# Main.net
KiCad netlist of a schematic drawn in Altium Designer
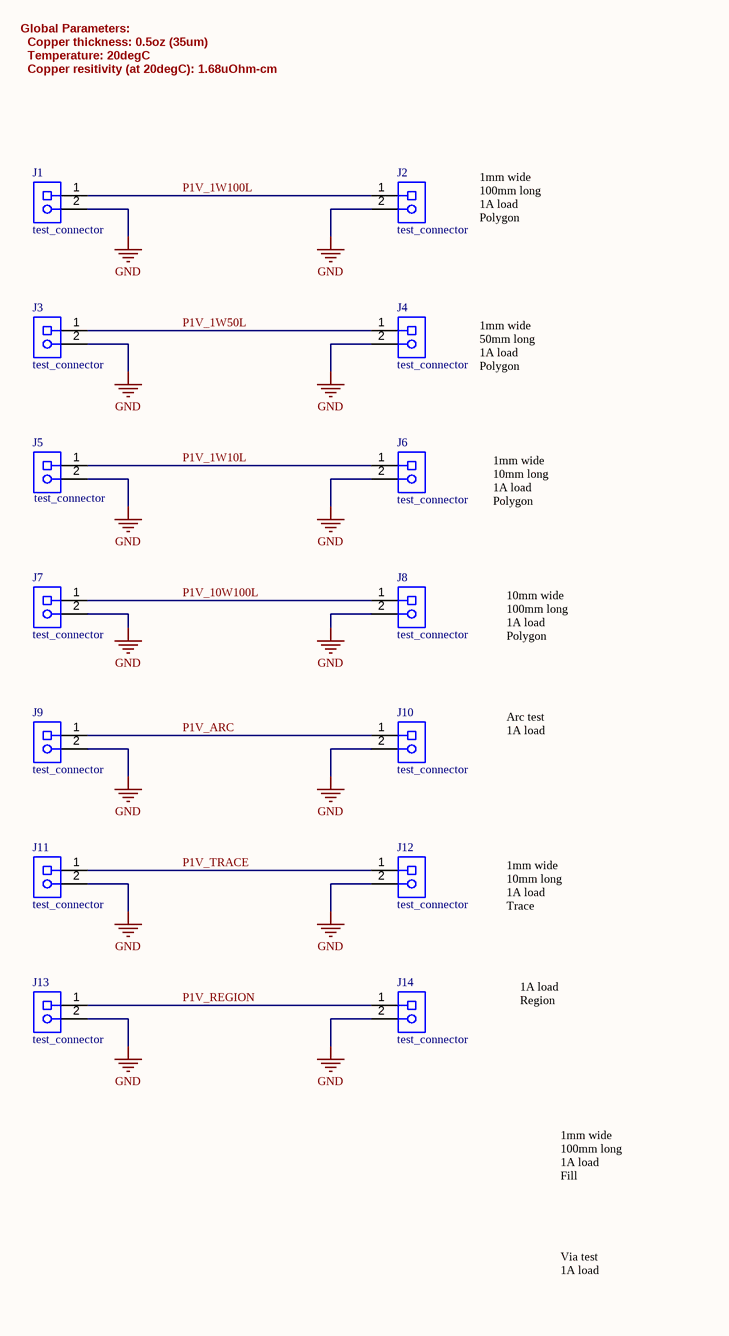
[diagram p0: Main.SchDoc]

(export (version "E")
  (design (tool "Eeschema 10.0.6"))
  (components
    (comp (ref "J1")
      (value "test_connector")
      (footprint "test_connector_footprint")
      (description "for playing around with")
      (fields
        (field (name "MANUFACTURER") "Phoenix Contact")
        (field (name "MANUFACTURER PART NUMBER") "1729128")
      )
      (libsource (lib "Sandbox") (part "test_conn"))
    )
    (comp (ref "J2")
      (value "test_connector")
      (footprint "test_connector_footprint")
      (description "for playing around with")
      (fields
        (field (name "MANUFACTURER") "Phoenix Contact")
        (field (name "MANUFACTURER PART NUMBER") "1729128")
      )
      (libsource (lib "") (part "test_conn_1"))
    )
    (comp (ref "J3")
      (value "test_connector")
      (footprint "test_connector_footprint")
      (description "for playing around with")
      (fields
        (field (name "MANUFACTURER") "Phoenix Contact")
        (field (name "MANUFACTURER PART NUMBER") "1729128")
      )
      (libsource (lib "Sandbox") (part "test_conn"))
    )
    (comp (ref "J4")
      (value "test_connector")
      (footprint "test_connector_footprint")
      (description "for playing around with")
      (fields
        (field (name "MANUFACTURER") "Phoenix Contact")
        (field (name "MANUFACTURER PART NUMBER") "1729128")
      )
      (libsource (lib "") (part "test_conn_1"))
    )
    (comp (ref "J5")
      (value "test_connector")
      (footprint "test_connector_footprint")
      (description "for playing around with")
      (fields
        (field (name "MANUFACTURER") "Phoenix Contact")
        (field (name "MANUFACTURER PART NUMBER") "1729128")
      )
      (libsource (lib "Sandbox") (part "test_conn"))
    )
    (comp (ref "J6")
      (value "test_connector")
      (footprint "test_connector_footprint")
      (description "for playing around with")
      (fields
        (field (name "MANUFACTURER") "Phoenix Contact")
        (field (name "MANUFACTURER PART NUMBER") "1729128")
      )
      (libsource (lib "") (part "test_conn_1"))
    )
    (comp (ref "J7")
      (value "test_connector")
      (footprint "test_connector_footprint")
      (description "for playing around with")
      (fields
        (field (name "MANUFACTURER") "Phoenix Contact")
        (field (name "MANUFACTURER PART NUMBER") "1729128")
      )
      (libsource (lib "Sandbox") (part "test_conn"))
    )
    (comp (ref "J8")
      (value "test_connector")
      (footprint "test_connector_footprint")
      (description "for playing around with")
      (fields
        (field (name "MANUFACTURER") "Phoenix Contact")
        (field (name "MANUFACTURER PART NUMBER") "1729128")
      )
      (libsource (lib "") (part "test_conn_1"))
    )
    (comp (ref "J9")
      (value "test_connector")
      (footprint "test_connector_footprint")
      (description "for playing around with")
      (fields
        (field (name "MANUFACTURER") "Phoenix Contact")
        (field (name "MANUFACTURER PART NUMBER") "1729128")
      )
      (libsource (lib "Sandbox") (part "test_conn"))
    )
    (comp (ref "J10")
      (value "test_connector")
      (footprint "test_connector_footprint")
      (description "for playing around with")
      (fields
        (field (name "MANUFACTURER") "Phoenix Contact")
        (field (name "MANUFACTURER PART NUMBER") "1729128")
      )
      (libsource (lib "") (part "test_conn_1"))
    )
    (comp (ref "J11")
      (value "test_connector")
      (footprint "test_connector_footprint")
      (description "for playing around with")
      (fields
        (field (name "MANUFACTURER") "Phoenix Contact")
        (field (name "MANUFACTURER PART NUMBER") "1729128")
      )
      (libsource (lib "Sandbox") (part "test_conn"))
    )
    (comp (ref "J12")
      (value "test_connector")
      (footprint "test_connector_footprint")
      (description "for playing around with")
      (fields
        (field (name "MANUFACTURER") "Phoenix Contact")
        (field (name "MANUFACTURER PART NUMBER") "1729128")
      )
      (libsource (lib "") (part "test_conn_1"))
    )
    (comp (ref "J13")
      (value "test_connector")
      (footprint "test_connector_footprint")
      (description "for playing around with")
      (fields
        (field (name "MANUFACTURER") "Phoenix Contact")
        (field (name "MANUFACTURER PART NUMBER") "1729128")
      )
      (libsource (lib "Sandbox") (part "test_conn"))
    )
    (comp (ref "J14")
      (value "test_connector")
      (footprint "test_connector_footprint")
      (description "for playing around with")
      (fields
        (field (name "MANUFACTURER") "Phoenix Contact")
        (field (name "MANUFACTURER PART NUMBER") "1729128")
      )
      (libsource (lib "") (part "test_conn_1"))
    )
  )
  (nets
    (net (code "1") (name "/P1V_1W10L") (class "Default")
      (node (ref "J5") (pin "1") (pinfunction "1_1") (pintype "passive"))
      (node (ref "J6") (pin "1") (pinfunction "1_1") (pintype "passive"))
    )
    (net (code "2") (name "/P1V_1W50L") (class "Default")
      (node (ref "J3") (pin "1") (pinfunction "1_1") (pintype "passive"))
      (node (ref "J4") (pin "1") (pinfunction "1_1") (pintype "passive"))
    )
    (net (code "3") (name "/P1V_1W100L") (class "Default")
      (node (ref "J1") (pin "1") (pinfunction "1_1") (pintype "passive"))
      (node (ref "J2") (pin "1") (pinfunction "1_1") (pintype "passive"))
    )
    (net (code "4") (name "/P1V_10W100L") (class "Default")
      (node (ref "J7") (pin "1") (pinfunction "1_1") (pintype "passive"))
      (node (ref "J8") (pin "1") (pinfunction "1_1") (pintype "passive"))
    )
    (net (code "5") (name "/P1V_ARC") (class "Default")
      (node (ref "J10") (pin "1") (pinfunction "1_1") (pintype "passive"))
      (node (ref "J9") (pin "1") (pinfunction "1_1") (pintype "passive"))
    )
    (net (code "6") (name "/P1V_REGION") (class "Default")
      (node (ref "J13") (pin "1") (pinfunction "1_1") (pintype "passive"))
      (node (ref "J14") (pin "1") (pinfunction "1_1") (pintype "passive"))
    )
    (net (code "7") (name "/P1V_TRACE") (class "Default")
      (node (ref "J11") (pin "1") (pinfunction "1_1") (pintype "passive"))
      (node (ref "J12") (pin "1") (pinfunction "1_1") (pintype "passive"))
    )
    (net (code "8") (name "GND") (class "Default")
      (node (ref "J1") (pin "2") (pinfunction "2_2") (pintype "passive"))
      (node (ref "J10") (pin "2") (pinfunction "2_2") (pintype "passive"))
      (node (ref "J11") (pin "2") (pinfunction "2_2") (pintype "passive"))
      (node (ref "J12") (pin "2") (pinfunction "2_2") (pintype "passive"))
      (node (ref "J13") (pin "2") (pinfunction "2_2") (pintype "passive"))
      (node (ref "J14") (pin "2") (pinfunction "2_2") (pintype "passive"))
      (node (ref "J2") (pin "2") (pinfunction "2_2") (pintype "passive"))
      (node (ref "J3") (pin "2") (pinfunction "2_2") (pintype "passive"))
      (node (ref "J4") (pin "2") (pinfunction "2_2") (pintype "passive"))
      (node (ref "J5") (pin "2") (pinfunction "2_2") (pintype "passive"))
      (node (ref "J6") (pin "2") (pinfunction "2_2") (pintype "passive"))
      (node (ref "J7") (pin "2") (pinfunction "2_2") (pintype "passive"))
      (node (ref "J8") (pin "2") (pinfunction "2_2") (pintype "passive"))
      (node (ref "J9") (pin "2") (pinfunction "2_2") (pintype "passive"))
    )
  )
)
